# LOADS.net
KiCad netlist of a schematic drawn in Altium Designer
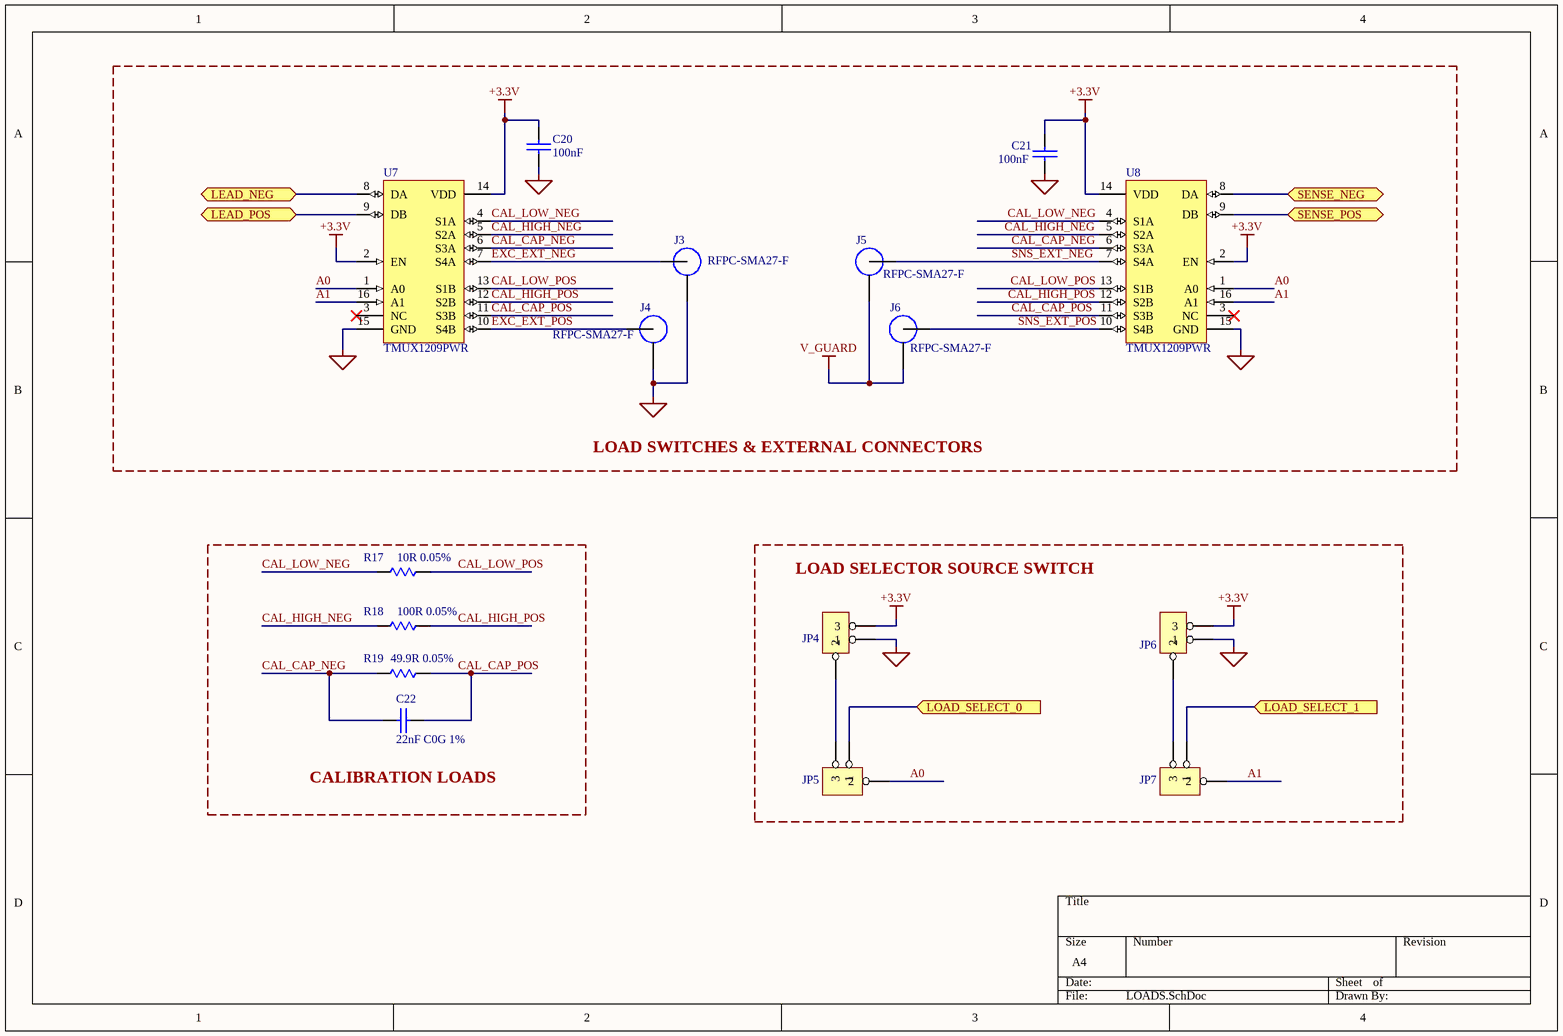
[diagram p0: LOADS.SchDoc]

(export (version "E")
  (design (tool "Eeschema 10.0.6"))
  (components
    (comp (ref "C20")
      (value "100nF")
      (footprint "0603-CAP")
      (description "CAP CER 100 NF 50V X7R 0603")
      (libsource (lib "SGL_Capacitors") (part "Capacitor"))
    )
    (comp (ref "C21")
      (value "100nF")
      (footprint "0603-CAP")
      (description "CAP CER 100 NF 50V X7R 0603")
      (libsource (lib "SGL_Capacitors") (part "Capacitor"))
    )
    (comp (ref "C22")
      (value "22nF C0G 1%")
      (footprint "0805-CAP")
      (description "CAP CER 0.022UF 50V C0G/NP0 0805")
      (libsource (lib "SGL_Capacitors") (part "Capacitor"))
    )
    (comp (ref "J3")
      (value "RFPC-SMA27-F")
      (footprint "GRADCONN_RFPC-SMA27-F")
      (fields (field (name "MF") "{'manufacturer': u'GCT (Gradconn)'}"))
      (libsource (lib "BioZ") (part "RFPC-SMA27-F"))
    )
    (comp (ref "J4")
      (value "RFPC-SMA27-F")
      (footprint "GRADCONN_RFPC-SMA27-F")
      (fields (field (name "MF") "{'manufacturer': u'GCT (Gradconn)'}"))
      (libsource (lib "BioZ") (part "RFPC-SMA27-F"))
    )
    (comp (ref "J5")
      (value "RFPC-SMA27-F")
      (footprint "GRADCONN_RFPC-SMA27-F")
      (fields (field (name "MF") "{'manufacturer': u'GCT (Gradconn)'}"))
      (libsource (lib "BioZ") (part "RFPC-SMA27-F"))
    )
    (comp (ref "J6")
      (value "RFPC-SMA27-F")
      (footprint "GRADCONN_RFPC-SMA27-F")
      (fields (field (name "MF") "{'manufacturer': u'GCT (Gradconn)'}"))
      (libsource (lib "BioZ") (part "RFPC-SMA27-F"))
    )
    (comp (ref "JP4")
      (value "JUMPER1X3")
      (footprint "JUMPER3")
      (description "CONN HEADER VERT 36POS 2.54MM")
      (libsource (lib "SGL_Connectors") (part "JUMPER1X3"))
    )
    (comp (ref "JP5")
      (value "JUMPER1X3")
      (footprint "JUMPER3")
      (description "CONN HEADER VERT 36POS 2.54MM")
      (libsource (lib "") (part "JUMPER1X3_1"))
    )
    (comp (ref "JP6")
      (value "JUMPER1X3")
      (footprint "JUMPER3")
      (description "CONN HEADER VERT 36POS 2.54MM")
      (libsource (lib "SGL_Connectors") (part "JUMPER1X3"))
    )
    (comp (ref "JP7")
      (value "JUMPER1X3")
      (footprint "JUMPER3")
      (description "CONN HEADER VERT 36POS 2.54MM")
      (libsource (lib "") (part "JUMPER1X3_1"))
    )
    (comp (ref "R17")
      (value "10R 0.05%")
      (footprint "0603-RES")
      (description "RES SMD 10OHM 0.05% 1/10W 0603")
      (libsource (lib "SGL_Resistives") (part "RESISTOR"))
    )
    (comp (ref "R18")
      (value "100R 0.05%")
      (footprint "0603-RES")
      (description "RES SMD 100OHM 0.05% 1/10W 0603")
      (libsource (lib "SGL_Resistives") (part "RESISTOR"))
    )
    (comp (ref "R19")
      (value "49.9R 0.05%")
      (footprint "0603-RES")
      (description "RES SMD 49.9OHM 0.05% 1/10W 0603")
      (libsource (lib "SGL_Resistives") (part "RESISTOR"))
    )
    (comp (ref "U7")
      (value "TMUX1209PWR")
      (footprint "PW0016A_N")
      (description "5-V, 4:1, 2-channel general-purpose multiplexer with 1.8-V input logic control 16-TSSOP -40 to 125")
      (fields (field (name "COPYRIGHT") "Copyright (C) 2025 Ultra Librarian. All rights reserved."))
      (libsource (lib "BioZ") (part "TMUX1209PWR"))
    )
    (comp (ref "U8")
      (value "TMUX1209PWR")
      (footprint "PW0016A_N")
      (description "5-V, 4:1, 2-channel general-purpose multiplexer with 1.8-V input logic control 16-TSSOP -40 to 125")
      (fields (field (name "COPYRIGHT") "Copyright (C) 2025 Ultra Librarian. All rights reserved."))
      (libsource (lib "") (part "TMUX1209PWR_1"))
    )
  )
  (nets
    (net (code "1") (name "+3.3V") (class "Default")
      (node (ref "C20") (pin "1") (pinfunction "1_1") (pintype "passive"))
      (node (ref "C21") (pin "1") (pinfunction "1_1") (pintype "passive"))
      (node (ref "JP4") (pin "3") (pinfunction "3_3") (pintype "passive"))
      (node (ref "JP6") (pin "3") (pinfunction "3_3") (pintype "passive"))
      (node (ref "U7") (pin "14") (pinfunction "VDD_14") (pintype "power_in"))
      (node (ref "U7") (pin "2") (pinfunction "EN_2") (pintype "input"))
      (node (ref "U8") (pin "14") (pinfunction "VDD_14") (pintype "power_in"))
      (node (ref "U8") (pin "2") (pinfunction "EN_2") (pintype "input"))
    )
    (net (code "2") (name "/A0") (class "Default")
      (node (ref "JP5") (pin "2") (pinfunction "2_2") (pintype "passive"))
      (node (ref "U7") (pin "1") (pinfunction "A0_1") (pintype "input"))
      (node (ref "U8") (pin "1") (pinfunction "A0_1") (pintype "input"))
    )
    (net (code "3") (name "/A1") (class "Default")
      (node (ref "JP7") (pin "2") (pinfunction "2_2") (pintype "passive"))
      (node (ref "U7") (pin "16") (pinfunction "A1_16") (pintype "input"))
      (node (ref "U8") (pin "16") (pinfunction "A1_16") (pintype "input"))
    )
    (net (code "4") (name "/CAL_CAP_NEG") (class "Default")
      (node (ref "C22") (pin "1") (pinfunction "1_1") (pintype "passive"))
      (node (ref "R19") (pin "1") (pinfunction "1_1") (pintype "passive"))
      (node (ref "U7") (pin "6") (pinfunction "S3A_6") (pintype "bidirectional"))
      (node (ref "U8") (pin "6") (pinfunction "S3A_6") (pintype "bidirectional"))
    )
    (net (code "5") (name "/CAL_CAP_POS") (class "Default")
      (node (ref "C22") (pin "2") (pinfunction "2_2") (pintype "passive"))
      (node (ref "R19") (pin "2") (pinfunction "2_2") (pintype "passive"))
      (node (ref "U7") (pin "11") (pinfunction "S3B_11") (pintype "bidirectional"))
      (node (ref "U8") (pin "11") (pinfunction "S3B_11") (pintype "bidirectional"))
    )
    (net (code "6") (name "/CAL_HIGH_NEG") (class "Default")
      (node (ref "R18") (pin "1") (pinfunction "1_1") (pintype "passive"))
      (node (ref "U7") (pin "5") (pinfunction "S2A_5") (pintype "bidirectional"))
      (node (ref "U8") (pin "5") (pinfunction "S2A_5") (pintype "bidirectional"))
    )
    (net (code "7") (name "/CAL_HIGH_POS") (class "Default")
      (node (ref "R18") (pin "2") (pinfunction "2_2") (pintype "passive"))
      (node (ref "U7") (pin "12") (pinfunction "S2B_12") (pintype "bidirectional"))
      (node (ref "U8") (pin "12") (pinfunction "S2B_12") (pintype "bidirectional"))
    )
    (net (code "8") (name "/CAL_LOW_NEG") (class "Default")
      (node (ref "R17") (pin "1") (pinfunction "1_1") (pintype "passive"))
      (node (ref "U7") (pin "4") (pinfunction "S1A_4") (pintype "bidirectional"))
      (node (ref "U8") (pin "4") (pinfunction "S1A_4") (pintype "bidirectional"))
    )
    (net (code "9") (name "/CAL_LOW_POS") (class "Default")
      (node (ref "R17") (pin "2") (pinfunction "2_2") (pintype "passive"))
      (node (ref "U7") (pin "13") (pinfunction "S1B_13") (pintype "bidirectional"))
      (node (ref "U8") (pin "13") (pinfunction "S1B_13") (pintype "bidirectional"))
    )
    (net (code "10") (name "/EXC_EXT_NEG") (class "Default")
      (node (ref "J3") (pin "SIG") (pinfunction "SIG_SIG") (pintype "passive"))
      (node (ref "U7") (pin "7") (pinfunction "S4A_7") (pintype "bidirectional"))
    )
    (net (code "11") (name "/EXC_EXT_POS") (class "Default")
      (node (ref "J4") (pin "SIG") (pinfunction "SIG_SIG") (pintype "passive"))
      (node (ref "U7") (pin "10") (pinfunction "S4B_10") (pintype "bidirectional"))
    )
    (net (code "12") (name "/LEAD_NEG") (class "Default")
      (node (ref "U7") (pin "8") (pinfunction "DA_8") (pintype "bidirectional"))
    )
    (net (code "13") (name "/LEAD_POS") (class "Default")
      (node (ref "U7") (pin "9") (pinfunction "DB_9") (pintype "bidirectional"))
    )
    (net (code "14") (name "/LOAD_SELECT_0") (class "Default")
      (node (ref "JP5") (pin "1") (pinfunction "1_1") (pintype "passive"))
    )
    (net (code "15") (name "/LOAD_SELECT_1") (class "Default")
      (node (ref "JP7") (pin "1") (pinfunction "1_1") (pintype "passive"))
    )
    (net (code "16") (name "/SENSE_NEG") (class "Default")
      (node (ref "U8") (pin "8") (pinfunction "DA_8") (pintype "bidirectional"))
    )
    (net (code "17") (name "/SENSE_POS") (class "Default")
      (node (ref "U8") (pin "9") (pinfunction "DB_9") (pintype "bidirectional"))
    )
    (net (code "18") (name "/SNS_EXT_NEG") (class "Default")
      (node (ref "J5") (pin "SIG") (pinfunction "SIG_SIG") (pintype "passive"))
      (node (ref "U8") (pin "7") (pinfunction "S4A_7") (pintype "bidirectional"))
    )
    (net (code "19") (name "/SNS_EXT_POS") (class "Default")
      (node (ref "J6") (pin "SIG") (pinfunction "SIG_SIG") (pintype "passive"))
      (node (ref "U8") (pin "10") (pinfunction "S4B_10") (pintype "bidirectional"))
    )
    (net (code "20") (name "GND") (class "Default")
      (node (ref "C20") (pin "2") (pinfunction "2_2") (pintype "passive"))
      (node (ref "C21") (pin "2") (pinfunction "2_2") (pintype "passive"))
      (node (ref "J3") (pin "SHLD") (pinfunction "SHLD_SHLD") (pintype "power_in"))
      (node (ref "J4") (pin "SHLD") (pinfunction "SHLD_SHLD") (pintype "power_in"))
      (node (ref "JP4") (pin "1") (pinfunction "1_1") (pintype "passive"))
      (node (ref "JP6") (pin "1") (pinfunction "1_1") (pintype "passive"))
      (node (ref "U7") (pin "15") (pinfunction "GND_15") (pintype "power_in"))
      (node (ref "U8") (pin "15") (pinfunction "GND_15") (pintype "power_in"))
    )
    (net (code "21") (name "Net-(JP4-Pad2)") (class "Default")
      (node (ref "JP4") (pin "2") (pinfunction "2_2") (pintype "passive"))
      (node (ref "JP5") (pin "3") (pinfunction "3_3") (pintype "passive"))
    )
    (net (code "22") (name "Net-(JP6-Pad2)") (class "Default")
      (node (ref "JP6") (pin "2") (pinfunction "2_2") (pintype "passive"))
      (node (ref "JP7") (pin "3") (pinfunction "3_3") (pintype "passive"))
    )
    (net (code "23") (name "V_GUARD") (class "Default")
      (node (ref "J5") (pin "SHLD") (pinfunction "SHLD_SHLD") (pintype "power_in"))
      (node (ref "J6") (pin "SHLD") (pinfunction "SHLD_SHLD") (pintype "power_in"))
    )
    (net (code "24") (name "unconnected-(U7-NC-Pad3)") (class "Default")
      (node (ref "U7") (pin "3") (pinfunction "NC_3") (pintype "passive+no_connect"))
    )
    (net (code "25") (name "unconnected-(U8-NC-Pad3)") (class "Default")
      (node (ref "U8") (pin "3") (pinfunction "NC_3") (pintype "passive+no_connect"))
    )
  )
)
